# Power.net
KiCad netlist of a schematic drawn in Altium Designer
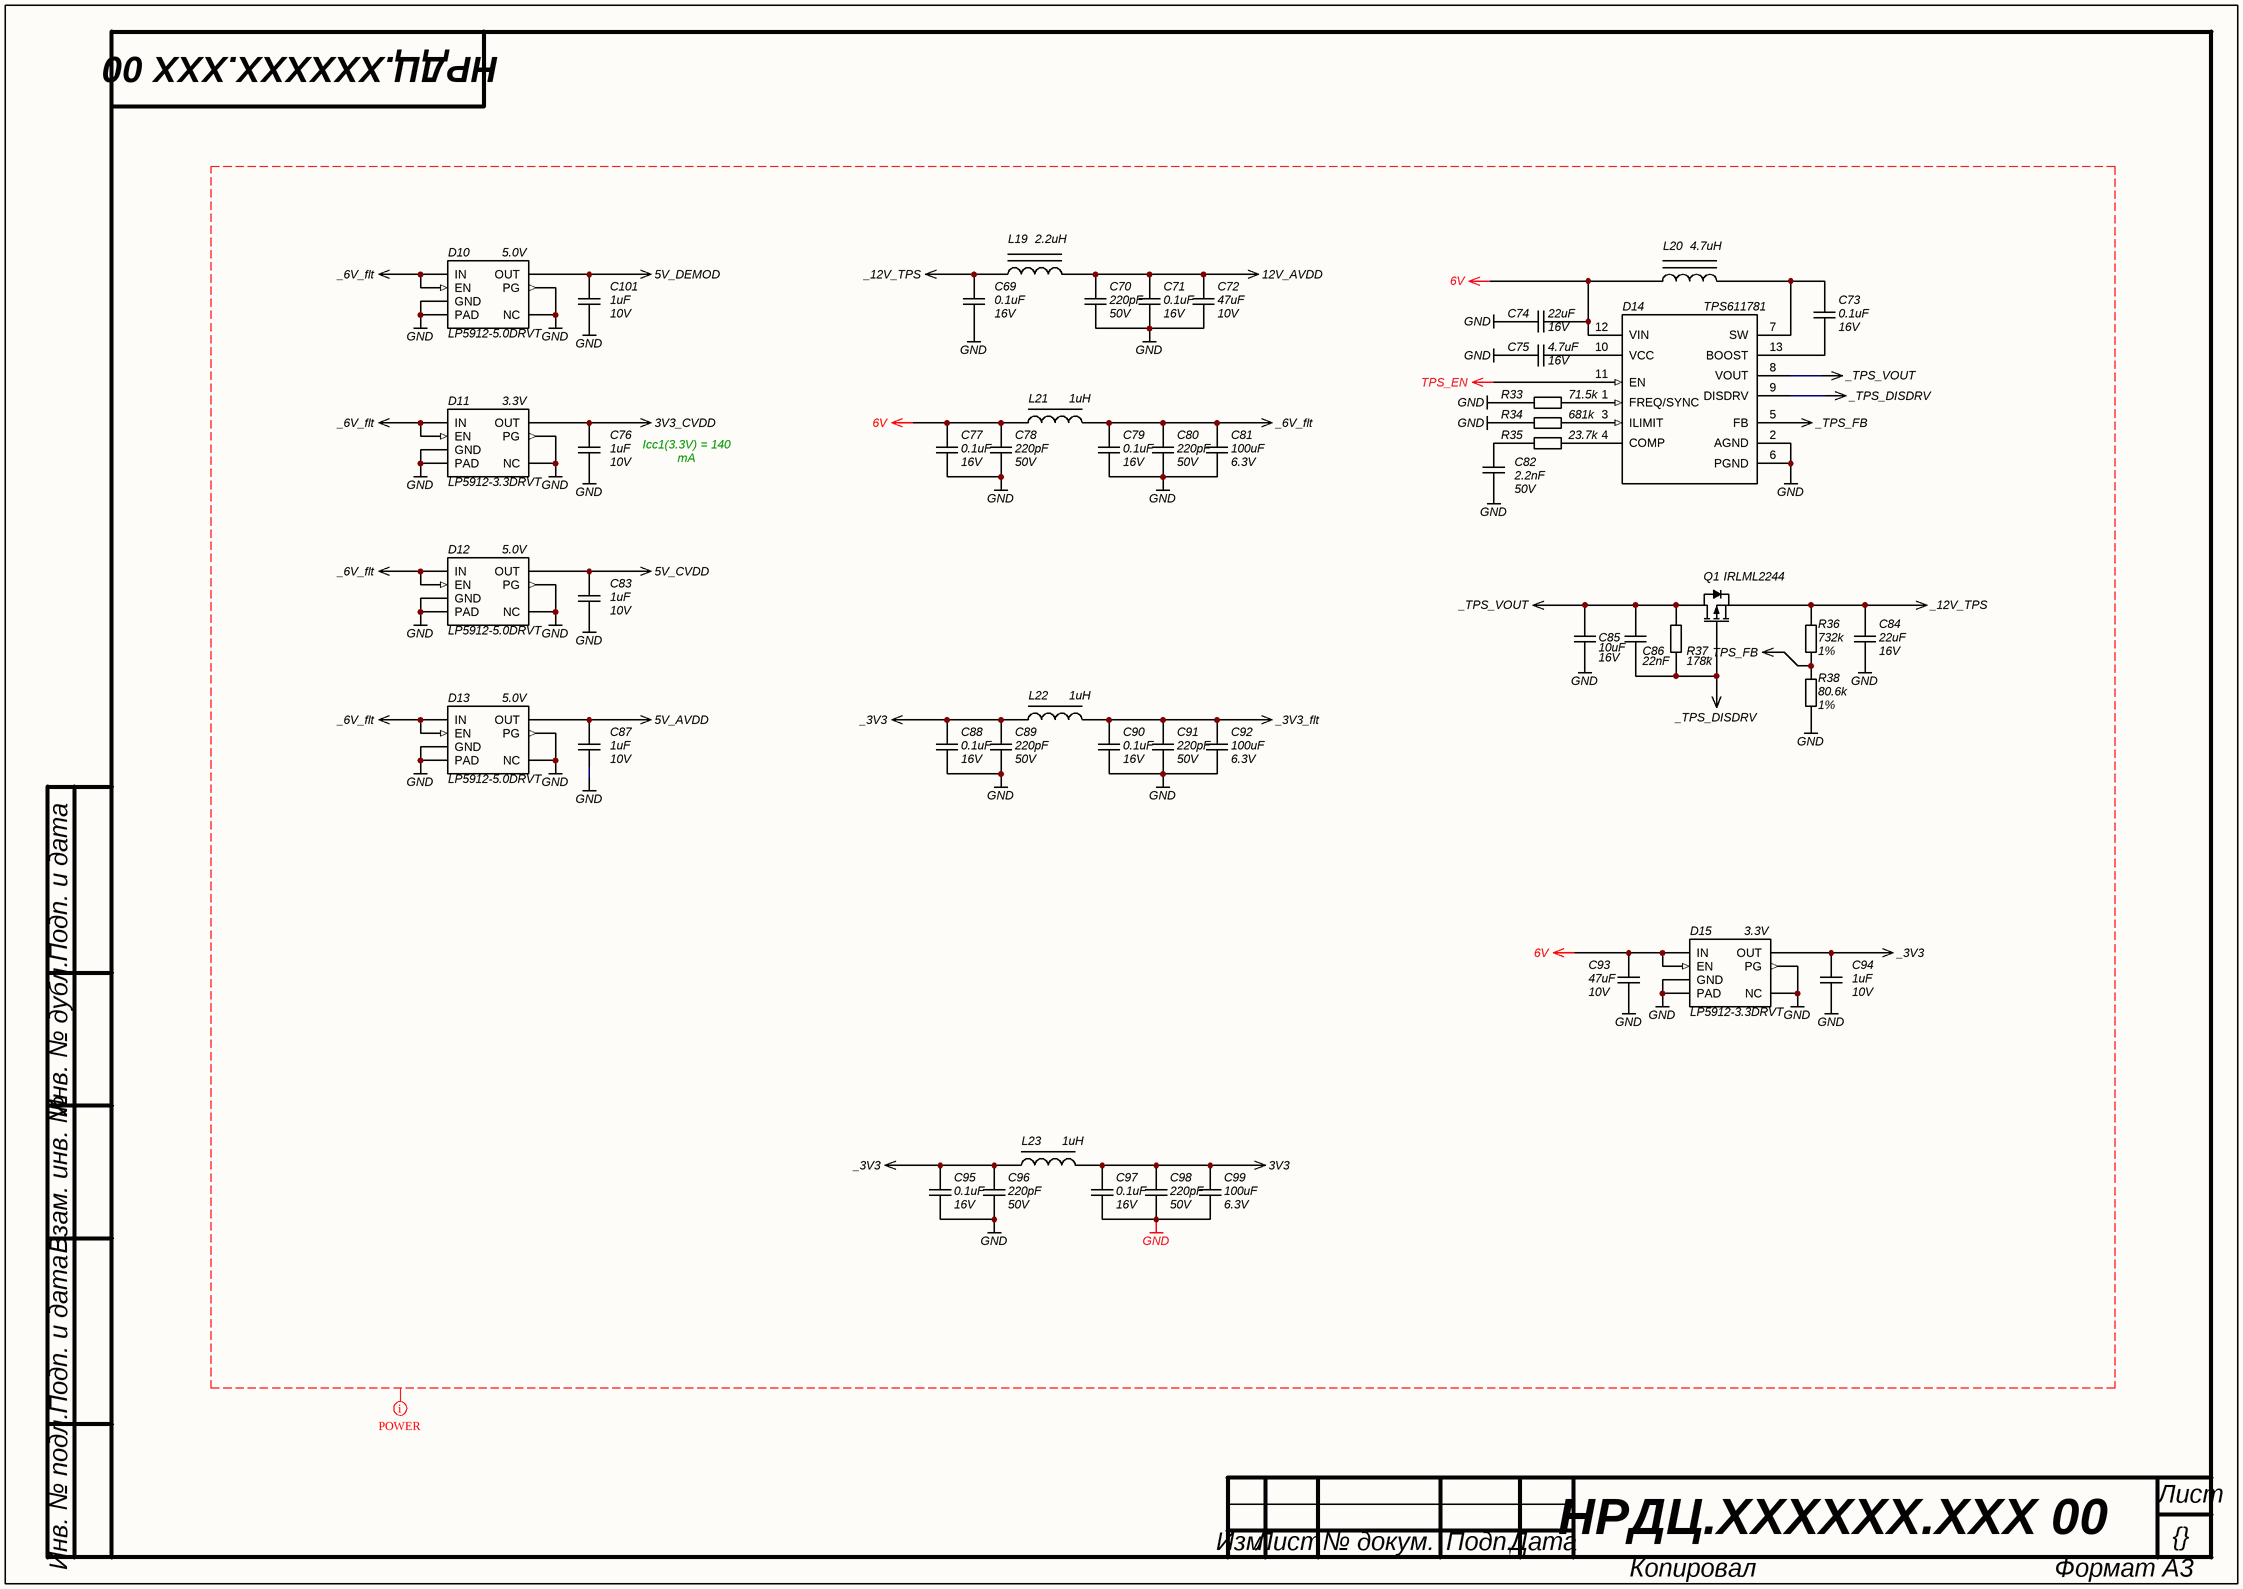
[diagram p0: Power.SchDoc]

(export (version "E")
  (design (tool "Eeschema 10.0.6"))
  (components
    (comp (ref "C69")
      (value "0.1uF")
      (footprint "C0402")
      (description "SMD Capacitor")
      (fields
        (field (name "MANUFACTURER") "Murata")
        (field (name "TOLERANCE") "±10%")
        (field (name "VOLTAGE") "16V")
      )
      (libsource (lib "Kintex_SDR") (part "CAP"))
    )
    (comp (ref "C70")
      (value "220pF")
      (footprint "C0603")
      (description "SMD Capacitor")
      (fields
        (field (name "MANUFACTURER") "Murata")
        (field (name "TOLERANCE") "10%")
        (field (name "VOLTAGE") "50V")
      )
      (libsource (lib "Kintex_SDR") (part "CAP"))
    )
    (comp (ref "C71")
      (value "0.1uF")
      (footprint "C0402")
      (description "SMD Capacitor")
      (fields
        (field (name "MANUFACTURER") "Murata")
        (field (name "TOLERANCE") "10%")
        (field (name "VOLTAGE") "16V")
      )
      (libsource (lib "Kintex_SDR") (part "CAP"))
    )
    (comp (ref "C72")
      (value "47uF")
      (footprint "C1210")
      (description "SMD Capacitor")
      (fields
        (field (name "MANUFACTURER") "Murata")
        (field (name "TOLERANCE") "10%")
        (field (name "VOLTAGE") "10V")
      )
      (libsource (lib "Kintex_SDR") (part "CAP uF"))
    )
    (comp (ref "C73")
      (value "0.1uF")
      (footprint "C0402")
      (description "SMD Capacitor")
      (fields
        (field (name "MANUFACTURER") "Murata")
        (field (name "TOLERANCE") "±10%")
        (field (name "VOLTAGE") "16V")
      )
      (libsource (lib "Kintex_SDR") (part "CAP"))
    )
    (comp (ref "C74")
      (value "22uF")
      (footprint "C0805")
      (description "SMD Capacitor")
      (fields
        (field (name "MANUFACTURER") "Murata")
        (field (name "TOLERANCE") "±20%")
        (field (name "VOLTAGE") "16V")
      )
      (libsource (lib "Kintex_SDR") (part "CAP uF"))
    )
    (comp (ref "C75")
      (value "4.7uF")
      (footprint "C0603")
      (description "SMD Capacitor")
      (fields
        (field (name "MANUFACTURER") "Murata")
        (field (name "TOLERANCE") "10%")
        (field (name "VOLTAGE") "16V")
      )
      (libsource (lib "Kintex_SDR") (part "CAP"))
    )
    (comp (ref "C76")
      (value "1uF")
      (footprint "C0805")
      (description "SMD Capacitor")
      (fields
        (field (name "MANUFACTURER") "Murata")
        (field (name "TOLERANCE") "10%")
        (field (name "VOLTAGE") "10V")
      )
      (libsource (lib "Kintex_SDR") (part "CAP"))
    )
    (comp (ref "C77")
      (value "0.1uF")
      (footprint "C0402")
      (description "SMD Capacitor")
      (fields
        (field (name "MANUFACTURER") "Murata")
        (field (name "TOLERANCE") "10%")
        (field (name "VOLTAGE") "16V")
      )
      (libsource (lib "Kintex_SDR") (part "CAP"))
    )
    (comp (ref "C78")
      (value "220pF")
      (footprint "C0603")
      (description "SMD Capacitor")
      (fields
        (field (name "MANUFACTURER") "Murata")
        (field (name "TOLERANCE") "10%")
        (field (name "VOLTAGE") "50V")
      )
      (libsource (lib "Kintex_SDR") (part "CAP"))
    )
    (comp (ref "C79")
      (value "0.1uF")
      (footprint "C0402")
      (description "SMD Capacitor")
      (fields
        (field (name "MANUFACTURER") "Murata")
        (field (name "TOLERANCE") "10%")
        (field (name "VOLTAGE") "16V")
      )
      (libsource (lib "Kintex_SDR") (part "CAP"))
    )
    (comp (ref "C80")
      (value "220pF")
      (footprint "C0603")
      (description "SMD Capacitor")
      (fields
        (field (name "MANUFACTURER") "Murata")
        (field (name "TOLERANCE") "10%")
        (field (name "VOLTAGE") "50V")
      )
      (libsource (lib "Kintex_SDR") (part "CAP"))
    )
    (comp (ref "C81")
      (value "100uF")
      (footprint "C1210")
      (description "SMD Capacitor")
      (fields
        (field (name "MANUFACTURER") "Murata")
        (field (name "TOLERANCE") "20%")
        (field (name "VOLTAGE") "6.3V")
      )
      (libsource (lib "Kintex_SDR") (part "CAP uF"))
    )
    (comp (ref "C82")
      (value "2.2nF")
      (footprint "C0603")
      (description "SMD Capacitor")
      (fields
        (field (name "MANUFACTURER") "Murata")
        (field (name "TOLERANCE") "±5%")
        (field (name "VOLTAGE") "50V")
      )
      (libsource (lib "Kintex_SDR") (part "CAP"))
    )
    (comp (ref "C83")
      (value "1uF")
      (footprint "C0805")
      (description "SMD Capacitor")
      (fields
        (field (name "MANUFACTURER") "Murata")
        (field (name "TOLERANCE") "10%")
        (field (name "VOLTAGE") "10V")
      )
      (libsource (lib "Kintex_SDR") (part "CAP"))
    )
    (comp (ref "C84")
      (value "22uF")
      (footprint "C0805")
      (description "SMD Capacitor")
      (fields
        (field (name "MANUFACTURER") "Murata")
        (field (name "TOLERANCE") "±20%")
        (field (name "VOLTAGE") "16V")
      )
      (libsource (lib "Kintex_SDR") (part "CAP uF"))
    )
    (comp (ref "C85")
      (value "10uF")
      (footprint "C0805")
      (description "SMD Capacitor")
      (fields
        (field (name "MANUFACTURER") "Murata")
        (field (name "TOLERANCE") "±10%")
        (field (name "VOLTAGE") "16V")
      )
      (libsource (lib "Kintex_SDR") (part "CAP uF"))
    )
    (comp (ref "C86")
      (value "22nF")
      (footprint "C0402")
      (description "SMD Capacitor")
      (fields (field (name "MANUFACTURER") "Murata") (field (name "TOLERANCE") "10%"))
      (libsource (lib "Kintex_SDR") (part "CAP"))
    )
    (comp (ref "C87")
      (value "1uF")
      (footprint "C0805")
      (description "SMD Capacitor")
      (fields
        (field (name "MANUFACTURER") "Murata")
        (field (name "TOLERANCE") "10%")
        (field (name "VOLTAGE") "10V")
      )
      (libsource (lib "Kintex_SDR") (part "CAP"))
    )
    (comp (ref "C88")
      (value "0.1uF")
      (footprint "C0402")
      (description "SMD Capacitor")
      (fields
        (field (name "MANUFACTURER") "Murata")
        (field (name "TOLERANCE") "10%")
        (field (name "VOLTAGE") "16V")
      )
      (libsource (lib "Kintex_SDR") (part "CAP"))
    )
    (comp (ref "C89")
      (value "220pF")
      (footprint "C0603")
      (description "SMD Capacitor")
      (fields
        (field (name "MANUFACTURER") "Murata")
        (field (name "TOLERANCE") "10%")
        (field (name "VOLTAGE") "50V")
      )
      (libsource (lib "Kintex_SDR") (part "CAP"))
    )
    (comp (ref "C90")
      (value "0.1uF")
      (footprint "C0402")
      (description "SMD Capacitor")
      (fields
        (field (name "MANUFACTURER") "Murata")
        (field (name "TOLERANCE") "10%")
        (field (name "VOLTAGE") "16V")
      )
      (libsource (lib "Kintex_SDR") (part "CAP"))
    )
    (comp (ref "C91")
      (value "220pF")
      (footprint "C0603")
      (description "SMD Capacitor")
      (fields
        (field (name "MANUFACTURER") "Murata")
        (field (name "TOLERANCE") "10%")
        (field (name "VOLTAGE") "50V")
      )
      (libsource (lib "Kintex_SDR") (part "CAP"))
    )
    (comp (ref "C92")
      (value "100uF")
      (footprint "C1210")
      (description "SMD Capacitor")
      (fields
        (field (name "MANUFACTURER") "Murata")
        (field (name "TOLERANCE") "20%")
        (field (name "VOLTAGE") "6.3V")
      )
      (libsource (lib "Kintex_SDR") (part "CAP uF"))
    )
    (comp (ref "C93")
      (value "47uF")
      (footprint "C1210")
      (description "SMD Capacitor")
      (fields
        (field (name "MANUFACTURER") "Murata")
        (field (name "TOLERANCE") "10%")
        (field (name "VOLTAGE") "10V")
      )
      (libsource (lib "Kintex_SDR") (part "CAP uF"))
    )
    (comp (ref "C94")
      (value "1uF")
      (footprint "C0805")
      (description "SMD Capacitor")
      (fields
        (field (name "MANUFACTURER") "Murata")
        (field (name "TOLERANCE") "10%")
        (field (name "VOLTAGE") "10V")
      )
      (libsource (lib "Kintex_SDR") (part "CAP"))
    )
    (comp (ref "C95")
      (value "0.1uF")
      (footprint "C0402")
      (description "SMD Capacitor")
      (fields
        (field (name "MANUFACTURER") "Murata")
        (field (name "TOLERANCE") "10%")
        (field (name "VOLTAGE") "16V")
      )
      (libsource (lib "Kintex_SDR") (part "CAP"))
    )
    (comp (ref "C96")
      (value "220pF")
      (footprint "C0603")
      (description "SMD Capacitor")
      (fields
        (field (name "MANUFACTURER") "Murata")
        (field (name "TOLERANCE") "10%")
        (field (name "VOLTAGE") "50V")
      )
      (libsource (lib "Kintex_SDR") (part "CAP"))
    )
    (comp (ref "C97")
      (value "0.1uF")
      (footprint "C0402")
      (description "SMD Capacitor")
      (fields
        (field (name "MANUFACTURER") "Murata")
        (field (name "TOLERANCE") "10%")
        (field (name "VOLTAGE") "16V")
      )
      (libsource (lib "Kintex_SDR") (part "CAP"))
    )
    (comp (ref "C98")
      (value "220pF")
      (footprint "C0603")
      (description "SMD Capacitor")
      (fields
        (field (name "MANUFACTURER") "Murata")
        (field (name "TOLERANCE") "10%")
        (field (name "VOLTAGE") "50V")
      )
      (libsource (lib "Kintex_SDR") (part "CAP"))
    )
    (comp (ref "C99")
      (value "100uF")
      (footprint "C1210")
      (description "SMD Capacitor")
      (fields
        (field (name "MANUFACTURER") "Murata")
        (field (name "TOLERANCE") "20%")
        (field (name "VOLTAGE") "6.3V")
      )
      (libsource (lib "Kintex_SDR") (part "CAP uF"))
    )
    (comp (ref "C101")
      (value "1uF")
      (footprint "C0805")
      (description "SMD Capacitor")
      (fields
        (field (name "MANUFACTURER") "Murata")
        (field (name "TOLERANCE") "10%")
        (field (name "VOLTAGE") "10V")
      )
      (libsource (lib "Kintex_SDR") (part "CAP"))
    )
    (comp (ref "D10")
      (value "LP5912")
      (footprint "DBLib:WSON-6")
      (description "LP5912 500-mA Low-Noise, Low-IQ LDO")
      (fields
        (field (name "MANUFACTURER") "Texas Instruments")
        (field (name "NAME") "LP5912-5.0DRVT")
        (field (name "VOLTAGE") "5.0V")
      )
      (libsource (lib "DBLib") (part "LP5912"))
    )
    (comp (ref "D11")
      (value "LP5912")
      (footprint "DBLib:WSON-6")
      (description "LP5912 500-mA Low-Noise, Low-IQ LDO")
      (fields
        (field (name "MANUFACTURER") "Texas Instruments")
        (field (name "NAME") "LP5912-3.3DRVT")
        (field (name "VOLTAGE") "3.3V")
      )
      (libsource (lib "DBLib") (part "LP5912"))
    )
    (comp (ref "D12")
      (value "LP5912")
      (footprint "DBLib:WSON-6")
      (description "LP5912 500-mA Low-Noise, Low-IQ LDO")
      (fields
        (field (name "MANUFACTURER") "Texas Instruments")
        (field (name "NAME") "LP5912-5.0DRVT")
        (field (name "VOLTAGE") "5.0V")
      )
      (libsource (lib "DBLib") (part "LP5912"))
    )
    (comp (ref "D13")
      (value "LP5912")
      (footprint "DBLib:WSON-6")
      (description "LP5912 500-mA Low-Noise, Low-IQ LDO")
      (fields
        (field (name "MANUFACTURER") "Texas Instruments")
        (field (name "NAME") "LP5912-5.0DRVT")
        (field (name "VOLTAGE") "5.0V")
      )
      (libsource (lib "DBLib") (part "LP5912"))
    )
    (comp (ref "D14")
      (value "TPS611781")
      (footprint "DBLib:TPS611781x")
      (description "10-A Fully-Integrated Synchronous Boost with Load Disconnect Control")
      (fields (field (name "MANUFACTURER") "Texas Instruments") (field (name "VOLTAGE") "4.5 V to 20 V"))
      (libsource (lib "DBLib") (part "TPS611781"))
    )
    (comp (ref "D15")
      (value "LP5912")
      (footprint "DBLib:WSON-6")
      (description "LP5912 500-mA Low-Noise, Low-IQ LDO")
      (fields
        (field (name "MANUFACTURER") "Texas Instruments")
        (field (name "NAME") "LP5912-3.3DRVT")
        (field (name "VOLTAGE") "3.3V")
      )
      (libsource (lib "DBLib") (part "LP5912"))
    )
    (comp (ref "L19")
      (value "2.2uH")
      (footprint "XAL4020")
      (description "Magnetic-Core Inductor")
      (fields (field (name "MANUFACTURER") "Coilcraft") (field (name "TOLERANCE") "±30%"))
      (libsource (lib "Kintex_SDR") (part "Inductor PWR"))
    )
    (comp (ref "L20")
      (value "4.7uH")
      (footprint "XAL4030")
      (description "Magnetic-Core Inductor")
      (fields (field (name "MANUFACTURER") "Coilcraft") (field (name "TOLERANCE") "±30%"))
      (libsource (lib "Kintex_SDR") (part "Inductor PWR"))
    )
    (comp (ref "L21")
      (value "1uH")
      (footprint "L1210_Murata LQH")
      (description "Inductor Power Lines")
      (fields (field (name "MANUFACTURER") "Murata") (field (name "TOLERANCE") "5%"))
      (libsource (lib "Kintex_SDR") (part "Inductor LF"))
    )
    (comp (ref "L22")
      (value "1uH")
      (footprint "L1210_Murata LQH")
      (description "Inductor Power Lines")
      (fields (field (name "MANUFACTURER") "Murata") (field (name "TOLERANCE") "5%"))
      (libsource (lib "Kintex_SDR") (part "Inductor LF"))
    )
    (comp (ref "L23")
      (value "1uH")
      (footprint "L1210_Murata LQH")
      (description "Inductor Power Lines")
      (fields (field (name "MANUFACTURER") "Murata") (field (name "TOLERANCE") "5%"))
      (libsource (lib "Kintex_SDR") (part "Inductor LF"))
    )
    (comp (ref "Q1")
      (value "IRLML2244")
      (footprint "DBLib:SOT-23")
      (description "P-Channel MOSFET")
      (fields (field (name "VOLTAGE") "-20V"))
      (libsource (lib "DBLib") (part "IRLML2244"))
    )
    (comp (ref "R33")
      (value "71.5k")
      (footprint "R0402")
      (description "SMD Resistor")
      (fields (field (name "POWER") "0.063 Wt") (field (name "TOLERANCE") "1%"))
      (libsource (lib "") (part "RES_1"))
    )
    (comp (ref "R34")
      (value "681k")
      (footprint "R0402")
      (description "SMD Resistor")
      (fields (field (name "POWER") "0.063 Wt") (field (name "TOLERANCE") "1%"))
      (libsource (lib "") (part "RES_1"))
    )
    (comp (ref "R35")
      (value "23.7k")
      (footprint "R0603")
      (description "SMD Resistor")
      (fields (field (name "POWER") "0.1 Wt") (field (name "TOLERANCE") "1%"))
      (libsource (lib "") (part "RES_1"))
    )
    (comp (ref "R36")
      (value "732k")
      (footprint "R0402")
      (description "SMD Resistor")
      (fields
        (field (name "POWER") "0.063 Wt")
        (field (name "TOLERANCE") "1%")
        (field (name "MANUFACTURER") "Panasonic Electronic Components")
      )
      (libsource (lib "Kintex_SDR") (part "RES"))
    )
    (comp (ref "R37")
      (value "178k")
      (footprint "R0402")
      (description "SMD Resistor")
      (fields (field (name "POWER") "0.063 Wt") (field (name "TOLERANCE") "1%"))
      (libsource (lib "Kintex_SDR") (part "RES"))
    )
    (comp (ref "R38")
      (value "80.6k")
      (footprint "R0402")
      (description "SMD Resistor")
      (fields
        (field (name "POWER") "0.063 Wt")
        (field (name "TOLERANCE") "1%")
        (field (name "MANUFACTURER") "Panasonic Electronic Components")
      )
      (libsource (lib "Kintex_SDR") (part "RES"))
    )
  )
  (nets
    (net (code "1") (name "3V3") (class "Default")
      (node (ref "C97") (pin "2") (pinfunction "2_2") (pintype "passive"))
      (node (ref "C98") (pin "2") (pinfunction "2_2") (pintype "passive"))
      (node (ref "C99") (pin "2") (pinfunction "2_2") (pintype "passive"))
      (node (ref "L23") (pin "2") (pinfunction "2_2") (pintype "passive"))
    )
    (net (code "2") (name "3V3_CVDD") (class "Default")
      (node (ref "C76") (pin "1") (pinfunction "1_1") (pintype "passive"))
      (node (ref "D11") (pin "1") (pinfunction "OUT_1") (pintype "passive"))
    )
    (net (code "3") (name "5V_AVDD") (class "Default")
      (node (ref "C87") (pin "1") (pinfunction "1_1") (pintype "passive"))
      (node (ref "D13") (pin "1") (pinfunction "OUT_1") (pintype "passive"))
    )
    (net (code "4") (name "5V_CVDD") (class "Default")
      (node (ref "C83") (pin "1") (pinfunction "1_1") (pintype "passive"))
      (node (ref "D12") (pin "1") (pinfunction "OUT_1") (pintype "passive"))
    )
    (net (code "5") (name "5V_DEMOD") (class "Default")
      (node (ref "C101") (pin "1") (pinfunction "1_1") (pintype "passive"))
      (node (ref "D10") (pin "1") (pinfunction "OUT_1") (pintype "passive"))
    )
    (net (code "6") (name "6V") (class "Default")
      (node (ref "C74") (pin "1") (pinfunction "1_1") (pintype "passive"))
      (node (ref "C77") (pin "2") (pinfunction "2_2") (pintype "passive"))
      (node (ref "C78") (pin "2") (pinfunction "2_2") (pintype "passive"))
      (node (ref "C93") (pin "2") (pinfunction "2_2") (pintype "passive"))
      (node (ref "D14") (pin "12") (pinfunction "VIN_12") (pintype "passive"))
      (node (ref "D15") (pin "4") (pinfunction "EN_4") (pintype "input"))
      (node (ref "D15") (pin "6") (pinfunction "IN_6") (pintype "passive"))
      (node (ref "L20") (pin "1") (pinfunction "1_1") (pintype "passive"))
      (node (ref "L21") (pin "1") (pinfunction "1_1") (pintype "passive"))
    )
    (net (code "7") (name "12V_AVDD") (class "Default")
      (node (ref "C70") (pin "2") (pinfunction "2_2") (pintype "passive"))
      (node (ref "C71") (pin "2") (pinfunction "2_2") (pintype "passive"))
      (node (ref "C72") (pin "2") (pinfunction "2_2") (pintype "passive"))
      (node (ref "L19") (pin "2") (pinfunction "2_2") (pintype "passive"))
    )
    (net (code "8") (name "GND") (class "Default")
      (node (ref "C101") (pin "2") (pinfunction "2_2") (pintype "passive"))
      (node (ref "C69") (pin "1") (pinfunction "1_1") (pintype "passive"))
      (node (ref "C70") (pin "1") (pinfunction "1_1") (pintype "passive"))
      (node (ref "C71") (pin "1") (pinfunction "1_1") (pintype "passive"))
      (node (ref "C72") (pin "1") (pinfunction "1_1") (pintype "passive"))
      (node (ref "C74") (pin "2") (pinfunction "2_2") (pintype "passive"))
      (node (ref "C75") (pin "2") (pinfunction "2_2") (pintype "passive"))
      (node (ref "C76") (pin "2") (pinfunction "2_2") (pintype "passive"))
      (node (ref "C77") (pin "1") (pinfunction "1_1") (pintype "passive"))
      (node (ref "C78") (pin "1") (pinfunction "1_1") (pintype "passive"))
      (node (ref "C79") (pin "1") (pinfunction "1_1") (pintype "passive"))
      (node (ref "C80") (pin "1") (pinfunction "1_1") (pintype "passive"))
      (node (ref "C81") (pin "1") (pinfunction "1_1") (pintype "passive"))
      (node (ref "C82") (pin "1") (pinfunction "1_1") (pintype "passive"))
      (node (ref "C83") (pin "2") (pinfunction "2_2") (pintype "passive"))
      (node (ref "C84") (pin "1") (pinfunction "1_1") (pintype "passive"))
      (node (ref "C85") (pin "1") (pinfunction "1_1") (pintype "passive"))
      (node (ref "C87") (pin "2") (pinfunction "2_2") (pintype "passive"))
      (node (ref "C88") (pin "1") (pinfunction "1_1") (pintype "passive"))
      (node (ref "C89") (pin "1") (pinfunction "1_1") (pintype "passive"))
      (node (ref "C90") (pin "1") (pinfunction "1_1") (pintype "passive"))
      (node (ref "C91") (pin "1") (pinfunction "1_1") (pintype "passive"))
      (node (ref "C92") (pin "1") (pinfunction "1_1") (pintype "passive"))
      (node (ref "C93") (pin "1") (pinfunction "1_1") (pintype "passive"))
      (node (ref "C94") (pin "2") (pinfunction "2_2") (pintype "passive"))
      (node (ref "C95") (pin "1") (pinfunction "1_1") (pintype "passive"))
      (node (ref "C96") (pin "1") (pinfunction "1_1") (pintype "passive"))
      (node (ref "C97") (pin "1") (pinfunction "1_1") (pintype "passive"))
      (node (ref "C98") (pin "1") (pinfunction "1_1") (pintype "passive"))
      (node (ref "C99") (pin "1") (pinfunction "1_1") (pintype "passive"))
      (node (ref "D10") (pin "0") (pinfunction "PAD_0") (pintype "passive"))
      (node (ref "D10") (pin "2") (pinfunction "NC_2") (pintype "passive"))
      (node (ref "D10") (pin "3") (pinfunction "PG_3") (pintype "output"))
      (node (ref "D10") (pin "5") (pinfunction "GND_5") (pintype "passive"))
      (node (ref "D11") (pin "0") (pinfunction "PAD_0") (pintype "passive"))
      (node (ref "D11") (pin "2") (pinfunction "NC_2") (pintype "passive"))
      (node (ref "D11") (pin "3") (pinfunction "PG_3") (pintype "output"))
      (node (ref "D11") (pin "5") (pinfunction "GND_5") (pintype "passive"))
      (node (ref "D12") (pin "0") (pinfunction "PAD_0") (pintype "passive"))
      (node (ref "D12") (pin "2") (pinfunction "NC_2") (pintype "passive"))
      (node (ref "D12") (pin "3") (pinfunction "PG_3") (pintype "output"))
      (node (ref "D12") (pin "5") (pinfunction "GND_5") (pintype "passive"))
      (node (ref "D13") (pin "0") (pinfunction "PAD_0") (pintype "passive"))
      (node (ref "D13") (pin "2") (pinfunction "NC_2") (pintype "passive"))
      (node (ref "D13") (pin "3") (pinfunction "PG_3") (pintype "output"))
      (node (ref "D13") (pin "5") (pinfunction "GND_5") (pintype "passive"))
      (node (ref "D14") (pin "2") (pinfunction "AGND_2") (pintype "passive"))
      (node (ref "D14") (pin "6") (pinfunction "PGND_6") (pintype "passive"))
      (node (ref "D15") (pin "0") (pinfunction "PAD_0") (pintype "passive"))
      (node (ref "D15") (pin "2") (pinfunction "NC_2") (pintype "passive"))
      (node (ref "D15") (pin "3") (pinfunction "PG_3") (pintype "output"))
      (node (ref "D15") (pin "5") (pinfunction "GND_5") (pintype "passive"))
      (node (ref "R33") (pin "1") (pinfunction "1_1") (pintype "passive"))
      (node (ref "R34") (pin "1") (pinfunction "1_1") (pintype "passive"))
      (node (ref "R38") (pin "1") (pinfunction "1_1") (pintype "passive"))
    )
    (net (code "9") (name "Net-(C82-Pad2)") (class "Default")
      (node (ref "C82") (pin "2") (pinfunction "2_2") (pintype "passive"))
      (node (ref "R35") (pin "1") (pinfunction "1_1") (pintype "passive"))
    )
    (net (code "10") (name "Net-(D14-BOOST)") (class "Default")
      (node (ref "C73") (pin "1") (pinfunction "1_1") (pintype "passive"))
      (node (ref "D14") (pin "13") (pinfunction "BOOST_13") (pintype "passive"))
    )
    (net (code "11") (name "Net-(D14-COMP)") (class "Default")
      (node (ref "D14") (pin "4") (pinfunction "COMP_4") (pintype "passive"))
      (node (ref "R35") (pin "2") (pinfunction "2_2") (pintype "passive"))
    )
    (net (code "12") (name "Net-(D14-FREQ{slash}SYNC)") (class "Default")
      (node (ref "D14") (pin "1") (pinfunction "FREQ/SYNC_1") (pintype "input"))
      (node (ref "R33") (pin "2") (pinfunction "2_2") (pintype "passive"))
    )
    (net (code "13") (name "Net-(D14-ILIMIT)") (class "Default")
      (node (ref "D14") (pin "3") (pinfunction "ILIMIT_3") (pintype "input"))
      (node (ref "R34") (pin "2") (pinfunction "2_2") (pintype "passive"))
    )
    (net (code "14") (name "Net-(D14-SW)") (class "Default")
      (node (ref "C73") (pin "2") (pinfunction "2_2") (pintype "passive"))
      (node (ref "D14") (pin "7") (pinfunction "SW_7") (pintype "passive"))
      (node (ref "L20") (pin "2") (pinfunction "2_2") (pintype "passive"))
    )
    (net (code "15") (name "Net-(D14-VCC)") (class "Default")
      (node (ref "C75") (pin "1") (pinfunction "1_1") (pintype "passive"))
      (node (ref "D14") (pin "10") (pinfunction "VCC_10") (pintype "passive"))
    )
    (net (code "16") (name "TPS_EN") (class "Default")
      (node (ref "D14") (pin "11") (pinfunction "EN_11") (pintype "input"))
    )
    (net (code "17") (name "_3V3") (class "Default")
      (node (ref "C88") (pin "2") (pinfunction "2_2") (pintype "passive"))
      (node (ref "C89") (pin "2") (pinfunction "2_2") (pintype "passive"))
      (node (ref "C94") (pin "1") (pinfunction "1_1") (pintype "passive"))
      (node (ref "C95") (pin "2") (pinfunction "2_2") (pintype "passive"))
      (node (ref "C96") (pin "2") (pinfunction "2_2") (pintype "passive"))
      (node (ref "D15") (pin "1") (pinfunction "OUT_1") (pintype "passive"))
      (node (ref "L22") (pin "1") (pinfunction "1_1") (pintype "passive"))
      (node (ref "L23") (pin "1") (pinfunction "1_1") (pintype "passive"))
    )
    (net (code "18") (name "_3V3_flt") (class "Default")
      (node (ref "C90") (pin "2") (pinfunction "2_2") (pintype "passive"))
      (node (ref "C91") (pin "2") (pinfunction "2_2") (pintype "passive"))
      (node (ref "C92") (pin "2") (pinfunction "2_2") (pintype "passive"))
      (node (ref "L22") (pin "2") (pinfunction "2_2") (pintype "passive"))
    )
    (net (code "19") (name "_6V_flt") (class "Default")
      (node (ref "C79") (pin "2") (pinfunction "2_2") (pintype "passive"))
      (node (ref "C80") (pin "2") (pinfunction "2_2") (pintype "passive"))
      (node (ref "C81") (pin "2") (pinfunction "2_2") (pintype "passive"))
      (node (ref "D10") (pin "4") (pinfunction "EN_4") (pintype "input"))
      (node (ref "D10") (pin "6") (pinfunction "IN_6") (pintype "passive"))
      (node (ref "D11") (pin "4") (pinfunction "EN_4") (pintype "input"))
      (node (ref "D11") (pin "6") (pinfunction "IN_6") (pintype "passive"))
      (node (ref "D12") (pin "4") (pinfunction "EN_4") (pintype "input"))
      (node (ref "D12") (pin "6") (pinfunction "IN_6") (pintype "passive"))
      (node (ref "D13") (pin "4") (pinfunction "EN_4") (pintype "input"))
      (node (ref "D13") (pin "6") (pinfunction "IN_6") (pintype "passive"))
      (node (ref "L21") (pin "2") (pinfunction "2_2") (pintype "passive"))
    )
    (net (code "20") (name "_12V_TPS") (class "Default")
      (node (ref "C69") (pin "2") (pinfunction "2_2") (pintype "passive"))
      (node (ref "C84") (pin "2") (pinfunction "2_2") (pintype "passive"))
      (node (ref "L19") (pin "1") (pinfunction "1_1") (pintype "passive"))
      (node (ref "Q1") (pin "2") (pinfunction "S_2") (pintype "passive"))
      (node (ref "R36") (pin "2") (pinfunction "2_2") (pintype "passive"))
    )
    (net (code "21") (name "_TPS_DISDRV") (class "Default")
      (node (ref "C86") (pin "2") (pinfunction "2_2") (pintype "passive"))
      (node (ref "D14") (pin "9") (pinfunction "DISDRV_9") (pintype "passive"))
      (node (ref "Q1") (pin "1") (pinfunction "G_1") (pintype "passive"))
      (node (ref "R37") (pin "1") (pinfunction "1_1") (pintype "passive"))
    )
    (net (code "22") (name "_TPS_FB") (class "Default")
      (node (ref "D14") (pin "5") (pinfunction "FB_5") (pintype "passive"))
      (node (ref "R36") (pin "1") (pinfunction "1_1") (pintype "passive"))
      (node (ref "R38") (pin "2") (pinfunction "2_2") (pintype "passive"))
    )
    (net (code "23") (name "_TPS_VOUT") (class "Default")
      (node (ref "C85") (pin "2") (pinfunction "2_2") (pintype "passive"))
      (node (ref "C86") (pin "1") (pinfunction "1_1") (pintype "passive"))
      (node (ref "D14") (pin "8") (pinfunction "VOUT_8") (pintype "passive"))
      (node (ref "Q1") (pin "3") (pinfunction "D_3") (pintype "passive"))
      (node (ref "R37") (pin "2") (pinfunction "2_2") (pintype "passive"))
    )
  )
)
